# OliPCBv1.net
KiCad netlist of a schematic drawn in EAGLE
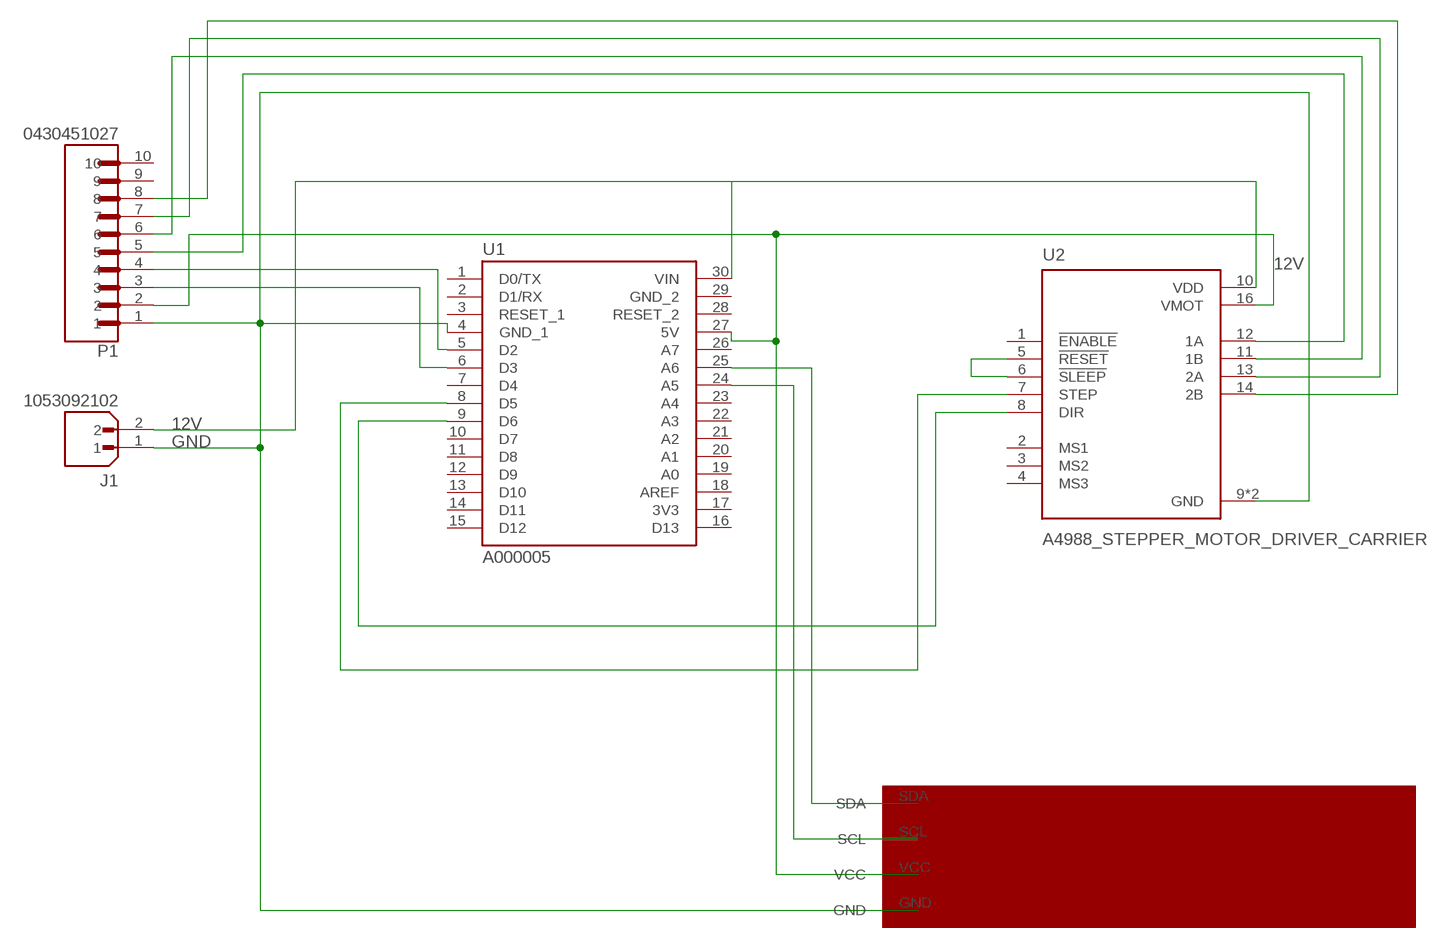
[diagram p0: schematic, sheet 1]

(export (version "E")
  (design (tool "Eeschema 10.0.6"))
  (components
    (comp (ref "J1")
      (value "1053092102")
      (footprint "eagle-import:MOLEX_1053092102")
      (fields (field (name "MF") "Molex"))
      (libsource (lib "eagle-import") (part "1053092102"))
    )
    (comp (ref "P1")
      (value "0430451027")
      (footprint "eagle-import:MOLEX_0430451027")
      (fields (field (name "MANUFACTURER") "Molex"))
      (libsource (lib "eagle-import") (part "0430451027"))
    )
    (comp (ref "U$1")
      (value "WYTP61_DEVICE")
      (footprint "eagle-import:WTYP61")
      (libsource (lib "eagle-import") (part "WYTP61_DEVICE"))
    )
    (comp (ref "U1")
      (value "A000005")
      (footprint "eagle-import:MODULE_A000005")
      (fields (field (name "MF") "Arduino"))
      (libsource (lib "eagle-import") (part "A000005"))
    )
    (comp (ref "U2")
      (value "A4988_STEPPER_MOTOR_DRIVER_CARRIER")
      (footprint "eagle-import:MODULE_A4988_STEPPER_MOTOR_DRIVER_CARRIER")
      (fields (field (name "MF") "Pololu") (field (name "MP") "A4988 STEPPER MOTOR DRIVER CARRIER"))
      (libsource (lib "eagle-import") (part "A4988_STEPPER_MOTOR_DRIVER_CARRIER"))
    )
  )
  (nets
    (net (code "1") (name "/3V3") (class "Default")
      (node (ref "U1") (pin "17") (pinfunction "3V3_17") (pintype "power_in"))
    )
    (net (code "2") (name "/12V") (class "Default")
      (node (ref "J1") (pin "2") (pinfunction "2_2") (pintype "passive"))
      (node (ref "U1") (pin "30") (pinfunction "VIN_30") (pintype "power_in"))
      (node (ref "U2") (pin "10") (pinfunction "VDD_10") (pintype "power_in"))
    )
    (net (code "3") (name "/GND") (class "Default")
      (node (ref "J1") (pin "1") (pinfunction "1_1") (pintype "passive"))
      (node (ref "P1") (pin "1") (pinfunction "1_1") (pintype "passive"))
      (node (ref "U$1") (pin "GND") (pinfunction "GND_GND") (pintype "bidirectional"))
      (node (ref "U1") (pin "4") (pinfunction "GND_1_4") (pintype "power_in"))
      (node (ref "U2") (pin "15") (pinfunction "GND_15") (pintype "power_in"))
      (node (ref "U2") (pin "9") (pinfunction "GND_9") (pintype "power_in"))
    )
    (net (code "4") (name "/GND_2") (class "Default")
      (node (ref "U1") (pin "29") (pinfunction "GND_2_29") (pintype "power_in"))
    )
    (net (code "5") (name "Net-(U1-5V)") (class "Default")
      (node (ref "P1") (pin "2") (pinfunction "2_2") (pintype "passive"))
      (node (ref "U$1") (pin "VCC") (pinfunction "VCC_VCC") (pintype "bidirectional"))
      (node (ref "U1") (pin "27") (pinfunction "5V_27") (pintype "power_in"))
      (node (ref "U2") (pin "16") (pinfunction "VMOT_16") (pintype "power_in"))
    )
    (net (code "6") (name "Net-(U1-A5)") (class "Default")
      (node (ref "U$1") (pin "SCL") (pinfunction "SCL_SCL") (pintype "bidirectional"))
      (node (ref "U1") (pin "24") (pinfunction "A5_24") (pintype "input"))
    )
    (net (code "7") (name "Net-(U1-A6)") (class "Default")
      (node (ref "U$1") (pin "SDA") (pinfunction "SDA_SDA") (pintype "bidirectional"))
      (node (ref "U1") (pin "25") (pinfunction "A6_25") (pintype "input"))
    )
    (net (code "8") (name "Net-(U1-D2)") (class "Default")
      (node (ref "P1") (pin "4") (pinfunction "4_4") (pintype "passive"))
      (node (ref "U1") (pin "5") (pinfunction "D2_5") (pintype "bidirectional"))
    )
    (net (code "9") (name "Net-(U1-D3)") (class "Default")
      (node (ref "P1") (pin "3") (pinfunction "3_3") (pintype "passive"))
      (node (ref "U1") (pin "6") (pinfunction "D3_6") (pintype "bidirectional"))
    )
    (net (code "10") (name "Net-(U1-D5)") (class "Default")
      (node (ref "U1") (pin "8") (pinfunction "D5_8") (pintype "bidirectional"))
      (node (ref "U2") (pin "7") (pinfunction "STEP_7") (pintype "input"))
    )
    (net (code "11") (name "Net-(U1-D6)") (class "Default")
      (node (ref "U1") (pin "9") (pinfunction "D6_9") (pintype "bidirectional"))
      (node (ref "U2") (pin "8") (pinfunction "DIR_8") (pintype "input"))
    )
    (net (code "12") (name "Net-(U2-1A)") (class "Default")
      (node (ref "P1") (pin "5") (pinfunction "5_5") (pintype "passive"))
      (node (ref "U2") (pin "12") (pinfunction "1A_12") (pintype "output"))
    )
    (net (code "13") (name "Net-(U2-1B)") (class "Default")
      (node (ref "P1") (pin "6") (pinfunction "6_6") (pintype "passive"))
      (node (ref "U2") (pin "11") (pinfunction "1B_11") (pintype "output"))
    )
    (net (code "14") (name "Net-(U2-2A)") (class "Default")
      (node (ref "P1") (pin "7") (pinfunction "7_7") (pintype "passive"))
      (node (ref "U2") (pin "13") (pinfunction "2A_13") (pintype "output"))
    )
    (net (code "15") (name "Net-(U2-2B)") (class "Default")
      (node (ref "P1") (pin "8") (pinfunction "8_8") (pintype "passive"))
      (node (ref "U2") (pin "14") (pinfunction "2B_14") (pintype "output"))
    )
    (net (code "16") (name "Net-(U2-~{RESET})") (class "Default")
      (node (ref "U2") (pin "5") (pinfunction "~{RESET}_5") (pintype "input"))
      (node (ref "U2") (pin "6") (pinfunction "~{SLEEP}_6") (pintype "input"))
    )
    (net (code "17") (name "unconnected-(P1-Pad9)") (class "Default")
      (node (ref "P1") (pin "9") (pinfunction "9_9") (pintype "passive"))
    )
    (net (code "18") (name "unconnected-(P1-Pad10)") (class "Default")
      (node (ref "P1") (pin "10") (pinfunction "10_10") (pintype "passive"))
    )
    (net (code "19") (name "unconnected-(U1-A0-Pad19)") (class "Default")
      (node (ref "U1") (pin "19") (pinfunction "A0_19") (pintype "input"))
    )
    (net (code "20") (name "unconnected-(U1-A1-Pad20)") (class "Default")
      (node (ref "U1") (pin "20") (pinfunction "A1_20") (pintype "input"))
    )
    (net (code "21") (name "unconnected-(U1-A2-Pad21)") (class "Default")
      (node (ref "U1") (pin "21") (pinfunction "A2_21") (pintype "input"))
    )
    (net (code "22") (name "unconnected-(U1-A3-Pad22)") (class "Default")
      (node (ref "U1") (pin "22") (pinfunction "A3_22") (pintype "input"))
    )
    (net (code "23") (name "unconnected-(U1-A4-Pad23)") (class "Default")
      (node (ref "U1") (pin "23") (pinfunction "A4_23") (pintype "input"))
    )
    (net (code "24") (name "unconnected-(U1-A7-Pad26)") (class "Default")
      (node (ref "U1") (pin "26") (pinfunction "A7_26") (pintype "input"))
    )
    (net (code "25") (name "unconnected-(U1-AREF-Pad18)") (class "Default")
      (node (ref "U1") (pin "18") (pinfunction "AREF_18") (pintype "input"))
    )
    (net (code "26") (name "unconnected-(U1-D0{slash}TX-Pad1)") (class "Default")
      (node (ref "U1") (pin "1") (pinfunction "D0/TX_1") (pintype "bidirectional"))
    )
    (net (code "27") (name "unconnected-(U1-D1{slash}RX-Pad2)") (class "Default")
      (node (ref "U1") (pin "2") (pinfunction "D1/RX_2") (pintype "bidirectional"))
    )
    (net (code "28") (name "unconnected-(U1-D4-Pad7)") (class "Default")
      (node (ref "U1") (pin "7") (pinfunction "D4_7") (pintype "bidirectional"))
    )
    (net (code "29") (name "unconnected-(U1-D7-Pad10)") (class "Default")
      (node (ref "U1") (pin "10") (pinfunction "D7_10") (pintype "bidirectional"))
    )
    (net (code "30") (name "unconnected-(U1-D8-Pad11)") (class "Default")
      (node (ref "U1") (pin "11") (pinfunction "D8_11") (pintype "bidirectional"))
    )
    (net (code "31") (name "unconnected-(U1-D9-Pad12)") (class "Default")
      (node (ref "U1") (pin "12") (pinfunction "D9_12") (pintype "bidirectional"))
    )
    (net (code "32") (name "unconnected-(U1-D10-Pad13)") (class "Default")
      (node (ref "U1") (pin "13") (pinfunction "D10_13") (pintype "bidirectional"))
    )
    (net (code "33") (name "unconnected-(U1-D11-Pad14)") (class "Default")
      (node (ref "U1") (pin "14") (pinfunction "D11_14") (pintype "bidirectional"))
    )
    (net (code "34") (name "unconnected-(U1-D12-Pad15)") (class "Default")
      (node (ref "U1") (pin "15") (pinfunction "D12_15") (pintype "bidirectional"))
    )
    (net (code "35") (name "unconnected-(U1-D13-Pad16)") (class "Default")
      (node (ref "U1") (pin "16") (pinfunction "D13_16") (pintype "bidirectional"))
    )
    (net (code "36") (name "unconnected-(U1-RESET_1-Pad3)") (class "Default")
      (node (ref "U1") (pin "3") (pinfunction "RESET_1_3") (pintype "input"))
    )
    (net (code "37") (name "unconnected-(U1-RESET_2-Pad28)") (class "Default")
      (node (ref "U1") (pin "28") (pinfunction "RESET_2_28") (pintype "input"))
    )
    (net (code "38") (name "unconnected-(U2-MS1-Pad2)") (class "Default")
      (node (ref "U2") (pin "2") (pinfunction "MS1_2") (pintype "input"))
    )
    (net (code "39") (name "unconnected-(U2-MS2-Pad3)") (class "Default")
      (node (ref "U2") (pin "3") (pinfunction "MS2_3") (pintype "input"))
    )
    (net (code "40") (name "unconnected-(U2-MS3-Pad4)") (class "Default")
      (node (ref "U2") (pin "4") (pinfunction "MS3_4") (pintype "input"))
    )
    (net (code "41") (name "unconnected-(U2-~{ENABLE}-Pad1)") (class "Default")
      (node (ref "U2") (pin "1") (pinfunction "~{ENABLE}_1") (pintype "input"))
    )
  )
)
